# EndCap_Board.net
KiCad netlist of a schematic drawn in EAGLE
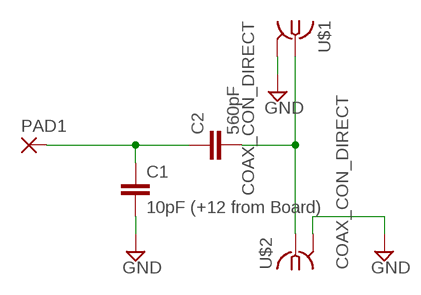
[diagram p0: schematic, sheet 1]

(export (version "E")
  (design (tool "Eeschema 10.0.6"))
  (components
    (comp (ref "C1")
      (value "10pF (+12 from Board)")
      (footprint "eagle-import:C1210")
      (libsource (lib "eagle-import") (part "C-EUC1210"))
    )
    (comp (ref "C2")
      (value "560pF")
      (footprint "eagle-import:C1210")
      (libsource (lib "eagle-import") (part "C-EUC1210"))
    )
    (comp (ref "PAD1")
      (value "SMD5")
      (footprint "eagle-import:SMD2,54-5,08")
      (libsource (lib "eagle-import") (part "SMD5"))
    )
    (comp (ref "U$1")
      (value "COAX_CON_DIRECT")
      (footprint "eagle-import:COAX.141")
      (libsource (lib "eagle-import") (part "COAX_CON_DIRECT"))
    )
    (comp (ref "U$2")
      (value "COAX_CON_DIRECT")
      (footprint "eagle-import:COAX.141")
      (libsource (lib "eagle-import") (part "COAX_CON_DIRECT"))
    )
  )
  (nets
    (net (code "1") (name "GND") (class "Default")
      (node (ref "C1") (pin "2") (pinfunction "2_2") (pintype "passive"))
      (node (ref "U$1") (pin "P$2") (pinfunction "GND_P$2") (pintype "passive"))
      (node (ref "U$2") (pin "P$2") (pinfunction "GND_P$2") (pintype "passive"))
    )
    (net (code "2") (name "Net-(PAD1-P)") (class "Default")
      (node (ref "C1") (pin "1") (pinfunction "1_1") (pintype "passive"))
      (node (ref "C2") (pin "1") (pinfunction "1_1") (pintype "passive"))
      (node (ref "PAD1") (pin "1") (pinfunction "P_1") (pintype "passive"))
    )
    (net (code "3") (name "Net-(U$1-1)") (class "Default")
      (node (ref "C2") (pin "2") (pinfunction "2_2") (pintype "passive"))
      (node (ref "U$1") (pin "P$1") (pinfunction "1_P$1") (pintype "passive"))
      (node (ref "U$2") (pin "P$1") (pinfunction "1_P$1") (pintype "passive"))
    )
  )
)
